# pc_fdc1004_brk_v3.net
KiCad netlist of a schematic drawn in EAGLE
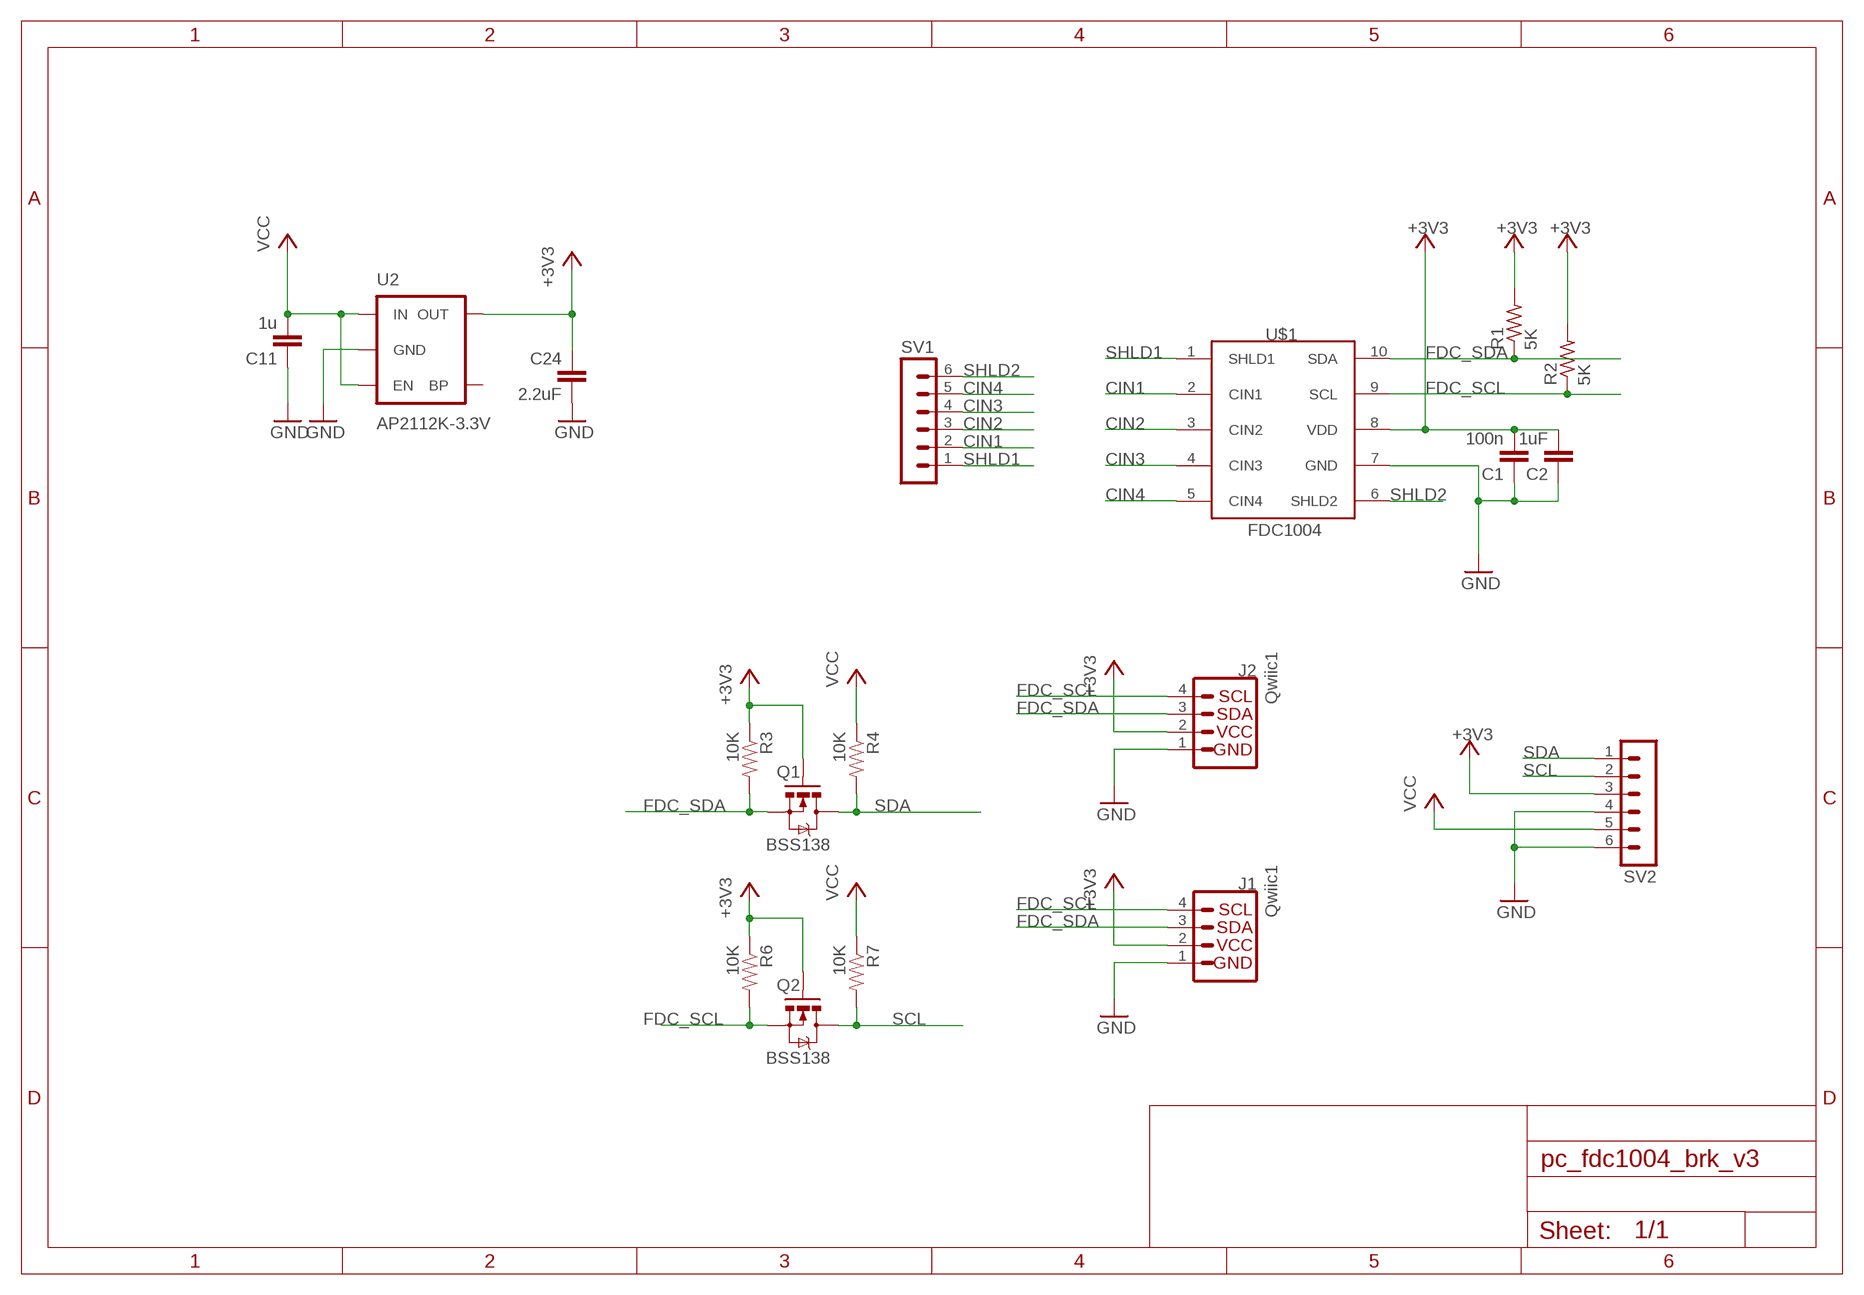
[diagram p0: schematic, sheet 1]

(export (version "E")
  (design (tool "Eeschema 10.0.6"))
  (components
    (comp (ref "C1")
      (value "100n")
      (footprint "eagle-import:C0805")
      (libsource (lib "eagle-import") (part "C-EUC0805"))
    )
    (comp (ref "C2")
      (value "1uF")
      (footprint "eagle-import:C0805")
      (libsource (lib "eagle-import") (part "C-EUC0805"))
    )
    (comp (ref "C11")
      (value "1u")
      (footprint "eagle-import:C0402")
      (libsource (lib "eagle-import") (part "C-EUC0402"))
    )
    (comp (ref "C24")
      (value "2.2uF")
      (footprint "eagle-import:C0402")
      (libsource (lib "eagle-import") (part "C-EUC0402"))
    )
    (comp (ref "J1")
      (value "Qwiic1")
      (footprint "eagle-import:1X04_1MM_RA")
      (libsource (lib "eagle-import") (part "QWIIC_CONNECTORJS-1MM"))
    )
    (comp (ref "J2")
      (value "Qwiic1")
      (footprint "eagle-import:1X04_1MM_RA")
      (libsource (lib "eagle-import") (part "QWIIC_CONNECTORJS-1MM"))
    )
    (comp (ref "Q1")
      (value "BSS138")
      (footprint "eagle-import:SOT23-3")
      (libsource (lib "eagle-import") (part "MOSFET-NCHANNELSMD"))
    )
    (comp (ref "Q2")
      (value "BSS138")
      (footprint "eagle-import:SOT23-3")
      (libsource (lib "eagle-import") (part "MOSFET-NCHANNELSMD"))
    )
    (comp (ref "R1")
      (value "5K")
      (footprint "eagle-import:R0805")
      (libsource (lib "eagle-import") (part "R-US_R0805"))
    )
    (comp (ref "R2")
      (value "5K")
      (footprint "eagle-import:R0805")
      (libsource (lib "eagle-import") (part "R-US_R0805"))
    )
    (comp (ref "R3")
      (value "10K")
      (footprint "eagle-import:0603-RES")
      (libsource (lib "eagle-import") (part "RESISTOR0603-RES"))
    )
    (comp (ref "R4")
      (value "10K")
      (footprint "eagle-import:0603-RES")
      (libsource (lib "eagle-import") (part "RESISTOR0603-RES"))
    )
    (comp (ref "R6")
      (value "10K")
      (footprint "eagle-import:0603-RES")
      (libsource (lib "eagle-import") (part "RESISTOR0603-RES"))
    )
    (comp (ref "R7")
      (value "10K")
      (footprint "eagle-import:0603-RES")
      (libsource (lib "eagle-import") (part "RESISTOR0603-RES"))
    )
    (comp (ref "SV1")
      (value "MA06-1")
      (footprint "eagle-import:MA06-1")
      (libsource (lib "eagle-import") (part "MA06-1"))
    )
    (comp (ref "SV2")
      (value "MA06-1")
      (footprint "eagle-import:MA06-1")
      (libsource (lib "eagle-import") (part "MA06-1"))
    )
    (comp (ref "U$1")
      (value "FDC1004")
      (footprint "eagle-import:VSSOP-10")
      (libsource (lib "eagle-import") (part "FDC1004"))
    )
    (comp (ref "U2")
      (value "AP2112K-3.3V")
      (footprint "eagle-import:SOT23-5")
      (libsource (lib "eagle-import") (part "V_REG_LDOSMD"))
    )
  )
  (nets
    (net (code "1") (name "+3V3") (class "Default")
      (node (ref "C1") (pin "2") (pinfunction "2_2") (pintype "passive"))
      (node (ref "C2") (pin "2") (pinfunction "2_2") (pintype "passive"))
      (node (ref "C24") (pin "1") (pinfunction "1_1") (pintype "passive"))
      (node (ref "J1") (pin "2") (pinfunction "2_2") (pintype "power_in"))
      (node (ref "J2") (pin "2") (pinfunction "2_2") (pintype "power_in"))
      (node (ref "Q1") (pin "1") (pinfunction "G_1") (pintype "passive"))
      (node (ref "Q2") (pin "1") (pinfunction "G_1") (pintype "passive"))
      (node (ref "R1") (pin "2") (pinfunction "2_2") (pintype "passive"))
      (node (ref "R2") (pin "2") (pinfunction "2_2") (pintype "passive"))
      (node (ref "R3") (pin "1") (pinfunction "1_1") (pintype "passive"))
      (node (ref "R6") (pin "1") (pinfunction "1_1") (pintype "passive"))
      (node (ref "SV2") (pin "3") (pinfunction "3_3") (pintype "passive"))
      (node (ref "U$1") (pin "8") (pinfunction "VDD_8") (pintype "bidirectional"))
      (node (ref "U2") (pin "5") (pinfunction "OUT_5") (pintype "passive"))
    )
    (net (code "2") (name "/CIN1") (class "Default")
      (node (ref "SV1") (pin "2") (pinfunction "2_2") (pintype "passive"))
      (node (ref "U$1") (pin "2") (pinfunction "CIN1_2") (pintype "bidirectional"))
    )
    (net (code "3") (name "/CIN2") (class "Default")
      (node (ref "SV1") (pin "3") (pinfunction "3_3") (pintype "passive"))
      (node (ref "U$1") (pin "3") (pinfunction "CIN2_3") (pintype "bidirectional"))
    )
    (net (code "4") (name "/CIN3") (class "Default")
      (node (ref "SV1") (pin "4") (pinfunction "4_4") (pintype "passive"))
      (node (ref "U$1") (pin "4") (pinfunction "CIN3_4") (pintype "bidirectional"))
    )
    (net (code "5") (name "/CIN4") (class "Default")
      (node (ref "SV1") (pin "5") (pinfunction "5_5") (pintype "passive"))
      (node (ref "U$1") (pin "5") (pinfunction "CIN4_5") (pintype "bidirectional"))
    )
    (net (code "6") (name "/FDC_SCL") (class "Default")
      (node (ref "J1") (pin "4") (pinfunction "4_4") (pintype "passive"))
      (node (ref "J2") (pin "4") (pinfunction "4_4") (pintype "passive"))
      (node (ref "Q2") (pin "2") (pinfunction "S_2") (pintype "passive"))
      (node (ref "R2") (pin "1") (pinfunction "1_1") (pintype "passive"))
      (node (ref "R6") (pin "2") (pinfunction "2_2") (pintype "passive"))
      (node (ref "U$1") (pin "9") (pinfunction "SCL_9") (pintype "bidirectional"))
    )
    (net (code "7") (name "/FDC_SDA") (class "Default")
      (node (ref "J1") (pin "3") (pinfunction "3_3") (pintype "passive"))
      (node (ref "J2") (pin "3") (pinfunction "3_3") (pintype "passive"))
      (node (ref "Q1") (pin "2") (pinfunction "S_2") (pintype "passive"))
      (node (ref "R1") (pin "1") (pinfunction "1_1") (pintype "passive"))
      (node (ref "R3") (pin "2") (pinfunction "2_2") (pintype "passive"))
      (node (ref "U$1") (pin "10") (pinfunction "SDA_10") (pintype "bidirectional"))
    )
    (net (code "8") (name "/SCL") (class "Default")
      (node (ref "Q2") (pin "3") (pinfunction "D_3") (pintype "passive"))
      (node (ref "R7") (pin "2") (pinfunction "2_2") (pintype "passive"))
      (node (ref "SV2") (pin "2") (pinfunction "2_2") (pintype "passive"))
    )
    (net (code "9") (name "/SDA") (class "Default")
      (node (ref "Q1") (pin "3") (pinfunction "D_3") (pintype "passive"))
      (node (ref "R4") (pin "2") (pinfunction "2_2") (pintype "passive"))
      (node (ref "SV2") (pin "1") (pinfunction "1_1") (pintype "passive"))
    )
    (net (code "10") (name "/SHLD1") (class "Default")
      (node (ref "SV1") (pin "1") (pinfunction "1_1") (pintype "passive"))
      (node (ref "U$1") (pin "1") (pinfunction "SHLD1_1") (pintype "bidirectional"))
    )
    (net (code "11") (name "/SHLD2") (class "Default")
      (node (ref "SV1") (pin "6") (pinfunction "6_6") (pintype "passive"))
      (node (ref "U$1") (pin "6") (pinfunction "SHLD2_6") (pintype "bidirectional"))
    )
    (net (code "12") (name "GND") (class "Default")
      (node (ref "C1") (pin "1") (pinfunction "1_1") (pintype "passive"))
      (node (ref "C11") (pin "1") (pinfunction "1_1") (pintype "passive"))
      (node (ref "C2") (pin "1") (pinfunction "1_1") (pintype "passive"))
      (node (ref "C24") (pin "2") (pinfunction "2_2") (pintype "passive"))
      (node (ref "J1") (pin "1") (pinfunction "1_1") (pintype "power_in"))
      (node (ref "J2") (pin "1") (pinfunction "1_1") (pintype "power_in"))
      (node (ref "SV2") (pin "4") (pinfunction "4_4") (pintype "passive"))
      (node (ref "SV2") (pin "6") (pinfunction "6_6") (pintype "passive"))
      (node (ref "U$1") (pin "7") (pinfunction "GND_7") (pintype "bidirectional"))
      (node (ref "U2") (pin "2") (pinfunction "GND_2") (pintype "input"))
    )
    (net (code "13") (name "VCC") (class "Default")
      (node (ref "C11") (pin "2") (pinfunction "2_2") (pintype "passive"))
      (node (ref "R4") (pin "1") (pinfunction "1_1") (pintype "passive"))
      (node (ref "R7") (pin "1") (pinfunction "1_1") (pintype "passive"))
      (node (ref "SV2") (pin "5") (pinfunction "5_5") (pintype "passive"))
      (node (ref "U2") (pin "1") (pinfunction "IN_1") (pintype "input"))
      (node (ref "U2") (pin "3") (pinfunction "EN_3") (pintype "input"))
    )
    (net (code "14") (name "unconnected-(U2-BP-Pad4)") (class "Default")
      (node (ref "U2") (pin "4") (pinfunction "BP_4") (pintype "input"))
    )
  )
)
